# Sheet1.net
KiCad netlist of a schematic drawn in Altium Designer
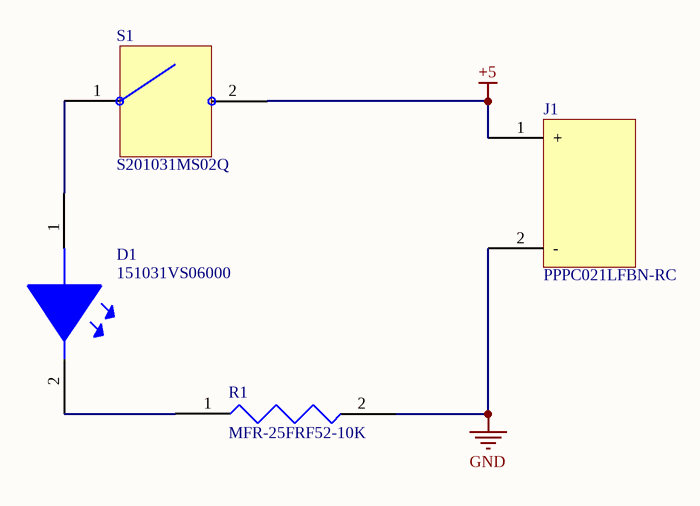
[diagram p0: Sheet1.SchDoc]

(export (version "E")
  (design (tool "Eeschema 10.0.6"))
  (components
    (comp (ref "D1")
      (value "151031VS06000")
      (footprint "LED")
      (description "Single Color LED, Bright Green, Diffused, T-1, 3mm")
      (fields (field (name "MANUFACTURER") "Wurth Electronics"))
      (libsource (lib "Schlib1") (part "151031VS06000"))
    )
    (comp (ref "J1")
      (value "PPPC021LFBN-RC")
      (footprint "HEAD")
      (fields (field (name "MANUFACTURER") "Sullins"))
      (libsource (lib "Schlib1") (part "PPPC021LFBN-RC"))
    )
    (comp (ref "R1")
      (value "MFR-25FRF52-10K")
      (footprint "RES")
      (description "Fixed Resistor, Metal Film, 0.25W, 10000ohm, 250V, 1% +/-Tol, 100ppm/Cel, Through Hole Mount")
      (fields (field (name "MANUFACTURER") "Yageo") (field (name "TOLERANCE") "1%"))
      (libsource (lib "Schlib1") (part "MFR-25FRF52-10K"))
    )
    (comp (ref "S1")
      (value "S201031MS02Q")
      (footprint "SW_S101031MS02Q")
      (fields (field (name "MANUFACTURER") "ITT C&K"))
      (libsource (lib "Schlib1") (part "S201031MS02Q"))
    )
  )
  (nets
    (net (code "1") (name "+5") (class "Default")
      (node (ref "J1") (pin "1") (pinfunction "+_1") (pintype "passive"))
      (node (ref "S1") (pin "2") (pinfunction "2_2") (pintype "passive"))
    )
    (net (code "2") (name "GND") (class "Default")
      (node (ref "J1") (pin "2") (pinfunction "-_2") (pintype "passive"))
      (node (ref "R1") (pin "2") (pinfunction "2_2") (pintype "passive"))
    )
    (net (code "3") (name "Net-(D1-Pad1)") (class "Default")
      (node (ref "D1") (pin "1") (pinfunction "1_1") (pintype "passive"))
      (node (ref "S1") (pin "1") (pinfunction "1_1") (pintype "passive"))
    )
    (net (code "4") (name "Net-(D1-Pad2)") (class "Default")
      (node (ref "D1") (pin "2") (pinfunction "2_2") (pintype "passive"))
      (node (ref "R1") (pin "1") (pinfunction "1_1") (pintype "passive"))
    )
  )
)
